# IN_conditioning.net
KiCad netlist of a schematic drawn in Altium Designer
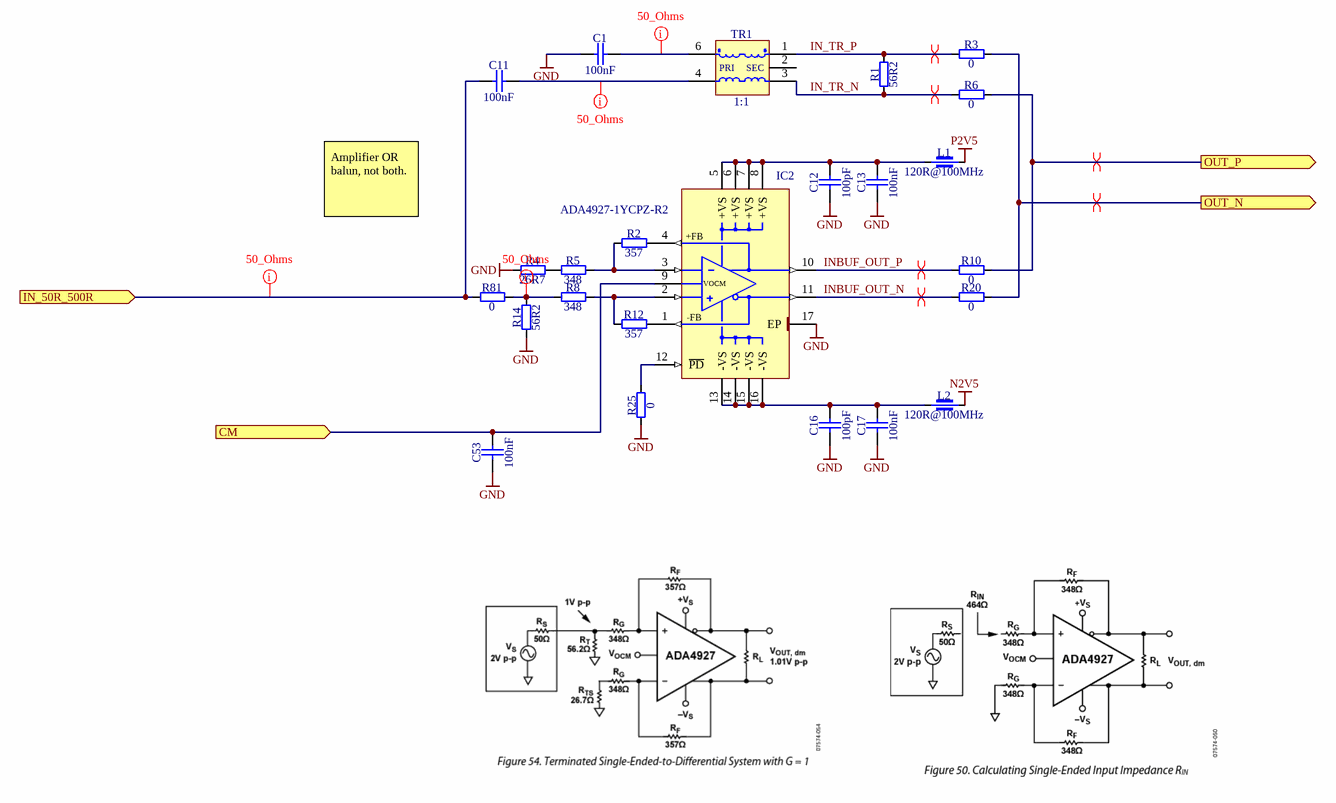
[diagram p0: IN_conditioning.SchDoc]

(export (version "E")
  (design (tool "Eeschema 10.0.6"))
  (components
    (comp (ref "C1")
      (value "100nF")
      (footprint "CAPC1005X55N")
      (description "Non-polarised capacitor")
      (fields
        (field (name "PART NUMBER") "CC0402_100NF_16V_10%_X5R")
        (field (name "VOLTAGE") "16V")
        (field (name "AUTHOR") "CERN DEM JLC")
      )
      (libsource (lib "Capacitors") (part "Capacitor - non polarized"))
    )
    (comp (ref "C11")
      (value "100nF")
      (footprint "CAPC1005X55N")
      (description "Non-polarised capacitor")
      (fields
        (field (name "PART NUMBER") "CC0402_100NF_16V_10%_X5R")
        (field (name "VOLTAGE") "16V")
        (field (name "AUTHOR") "CERN DEM JLC")
      )
      (libsource (lib "Capacitors") (part "Capacitor - non polarized"))
    )
    (comp (ref "C12")
      (value "100pF")
      (footprint "CAPC1005X55N")
      (description "Non-polarised capacitor")
      (fields
        (field (name "PART NUMBER") "CC0402_100PF_50V_2%_C0G")
        (field (name "VOLTAGE") "50V")
        (field (name "AUTHOR") "CERN DEM BC")
      )
      (libsource (lib "Capacitors") (part "Capacitor - non polarized"))
    )
    (comp (ref "C13")
      (value "100nF")
      (footprint "CAPC1005X55N")
      (description "Non-polarised capacitor")
      (fields
        (field (name "PART NUMBER") "CC0402_100NF_16V_10%_X5R")
        (field (name "VOLTAGE") "16V")
        (field (name "AUTHOR") "CERN DEM JLC")
      )
      (libsource (lib "Capacitors") (part "Capacitor - non polarized"))
    )
    (comp (ref "C16")
      (value "100pF")
      (footprint "CAPC1005X55N")
      (description "Non-polarised capacitor")
      (fields
        (field (name "PART NUMBER") "CC0402_100PF_50V_2%_C0G")
        (field (name "VOLTAGE") "50V")
        (field (name "AUTHOR") "CERN DEM BC")
      )
      (libsource (lib "Capacitors") (part "Capacitor - non polarized"))
    )
    (comp (ref "C17")
      (value "100nF")
      (footprint "CAPC1005X55N")
      (description "Non-polarised capacitor")
      (fields
        (field (name "PART NUMBER") "CC0402_100NF_16V_10%_X5R")
        (field (name "VOLTAGE") "16V")
        (field (name "AUTHOR") "CERN DEM JLC")
      )
      (libsource (lib "Capacitors") (part "Capacitor - non polarized"))
    )
    (comp (ref "C53")
      (value "100nF")
      (footprint "CAPC1005X55N")
      (description "Non-polarised capacitor")
      (fields
        (field (name "PART NUMBER") "CC0402_100NF_16V_10%_X5R")
        (field (name "VOLTAGE") "16V")
        (field (name "AUTHOR") "CERN DEM JLC")
      )
      (libsource (lib "Capacitors") (part "Capacitor - non polarized"))
    )
    (comp (ref "IC2")
      (value "ADA4927-1YCPZ-R2")
      (footprint "QFN50P300X300X100-17N-S145")
      (description "Ultralow Distortion Current Feedback Differential ADC Driver")
      (fields
        (field (name "MANUFACTURER") "ANALOG DEVICES")
        (field (name "MANUFACTURER PART NUMBER") "ADA4927-1YCP")
        (field (name "AUTHOR") "CERN DEM JLC")
      )
      (libsource (lib "ICs And Semiconductors") (part "ADA4927-1"))
    )
    (comp (ref "L1")
      (value "120R@100MHz")
      (footprint "INDC1005X55N")
      (fields
        (field (name "PART NUMBER") "IND0402_MURATA_BLM15PX121SN1D")
        (field (name "POWER") "2A")
        (field (name "TOLERANCE") "±25%")
        (field (name "AUTHOR") "CERN DEM JMW")
      )
      (libsource (lib "Inductors & Transformers") (part "Ferrite Bead"))
    )
    (comp (ref "L2")
      (value "120R@100MHz")
      (footprint "INDC1005X55N")
      (fields
        (field (name "PART NUMBER") "IND0402_MURATA_BLM15PX121SN1D")
        (field (name "POWER") "2A")
        (field (name "TOLERANCE") "±25%")
        (field (name "AUTHOR") "CERN DEM JMW")
      )
      (libsource (lib "Inductors & Transformers") (part "Ferrite Bead"))
    )
    (comp (ref "R1")
      (value "56R2")
      (footprint "RESC1005X40N")
      (description "Resistor - 1%")
      (fields
        (field (name "PART NUMBER") "R0402_56R2_1%_0.063W_50PPM")
        (field (name "MANUFACTURER") "GENERIC")
        (field (name "AUTHOR") "SHA")
      )
      (libsource (lib "Modulator_pLib") (part "R0402_56R2_1%_0.063W_50PPM"))
    )
    (comp (ref "R2")
      (value "357")
      (footprint "RESC1005X40N")
      (description "Resistor - 0.1%")
      (fields
        (field (name "PART NUMBER") "R0402_357R_0.1%_0.063W_25PPM")
        (field (name "MANUFACTURER") "GENERIC")
        (field (name "AUTHOR") "SHA")
      )
      (libsource (lib "Modulator_pLib") (part "R0402_357R_0.1%_0.063W_50PPM"))
    )
    (comp (ref "R3")
      (value "0")
      (footprint "RESC1005X40N")
      (description "Resistor")
      (fields
        (field (name "PART NUMBER") "R0402_0R_JUMPER")
        (field (name "MANUFACTURER") "GENERIC")
        (field (name "AUTHOR") "CERN DEM JLC")
      )
      (libsource (lib "Resistors") (part "Resistor"))
    )
    (comp (ref "R4")
      (value "26R7")
      (footprint "RESC1005X40N")
      (description "Resistor - 1%")
      (fields
        (field (name "PART NUMBER") "R0402_26R7_1%_0.063W_100PPM")
        (field (name "MANUFACTURER") "GENERIC")
        (field (name "AUTHOR") "SHA")
      )
      (libsource (lib "Modulator_pLib") (part "R0402_26R7_1%_0.063W_100PPM"))
    )
    (comp (ref "R5")
      (value "348")
      (footprint "RESC1005X40N")
      (description "Resistor - 0.1%")
      (fields
        (field (name "PART NUMBER") "R0402_348R_0.1%_0.063W_25PPM")
        (field (name "MANUFACTURER") "GENERIC")
        (field (name "AUTHOR") "SHA")
      )
      (libsource (lib "Modulator_pLib") (part "R0402_348R_0.1%_0.063W_25PPM"))
    )
    (comp (ref "R6")
      (value "0")
      (footprint "RESC1005X40N")
      (description "Resistor")
      (fields
        (field (name "PART NUMBER") "R0402_0R_JUMPER")
        (field (name "MANUFACTURER") "GENERIC")
        (field (name "AUTHOR") "CERN DEM JLC")
      )
      (libsource (lib "Resistors") (part "Resistor"))
    )
    (comp (ref "R8")
      (value "348")
      (footprint "RESC1005X40N")
      (description "Resistor - 0.1%")
      (fields
        (field (name "PART NUMBER") "R0402_348R_0.1%_0.063W_25PPM")
        (field (name "MANUFACTURER") "GENERIC")
        (field (name "AUTHOR") "SHA")
      )
      (libsource (lib "Modulator_pLib") (part "R0402_348R_0.1%_0.063W_25PPM"))
    )
    (comp (ref "R10")
      (value "0")
      (footprint "RESC1005X40N")
      (description "Resistor")
      (fields
        (field (name "PART NUMBER") "R0402_0R_JUMPER")
        (field (name "MANUFACTURER") "GENERIC")
        (field (name "AUTHOR") "CERN DEM JLC")
      )
      (libsource (lib "Resistors") (part "Resistor"))
    )
    (comp (ref "R12")
      (value "357")
      (footprint "RESC1005X40N")
      (description "Resistor - 0.1%")
      (fields
        (field (name "PART NUMBER") "R0402_357R_0.1%_0.063W_25PPM")
        (field (name "MANUFACTURER") "GENERIC")
        (field (name "AUTHOR") "SHA")
      )
      (libsource (lib "Modulator_pLib") (part "R0402_357R_0.1%_0.063W_50PPM"))
    )
    (comp (ref "R14")
      (value "56R2")
      (footprint "RESC1005X40N")
      (description "Resistor - 1%")
      (fields
        (field (name "PART NUMBER") "R0402_56R2_1%_0.063W_50PPM")
        (field (name "MANUFACTURER") "GENERIC")
        (field (name "AUTHOR") "SHA")
      )
      (libsource (lib "Modulator_pLib") (part "R0402_56R2_1%_0.063W_50PPM"))
    )
    (comp (ref "R20")
      (value "0")
      (footprint "RESC1005X40N")
      (description "Resistor")
      (fields
        (field (name "PART NUMBER") "R0402_0R_JUMPER")
        (field (name "MANUFACTURER") "GENERIC")
        (field (name "AUTHOR") "CERN DEM JLC")
      )
      (libsource (lib "Resistors") (part "Resistor"))
    )
    (comp (ref "R25")
      (value "0")
      (footprint "RESC1005X40N")
      (description "Resistor")
      (fields
        (field (name "PART NUMBER") "R0402_0R_JUMPER")
        (field (name "MANUFACTURER") "GENERIC")
        (field (name "AUTHOR") "CERN DEM JLC")
      )
      (libsource (lib "Resistors") (part "Resistor"))
    )
    (comp (ref "R81")
      (value "0")
      (footprint "RESC1005X40N")
      (description "Resistor")
      (fields
        (field (name "PART NUMBER") "R0402_0R_JUMPER")
        (field (name "MANUFACTURER") "GENERIC")
        (field (name "AUTHOR") "CERN DEM JLC")
      )
      (libsource (lib "Resistors") (part "Resistor"))
    )
    (comp (ref "TR1")
      (value "1:1")
      (footprint "XFMR_MINI-CIRCUITS_AT224")
      (description "50 Ohms 4.5 To 3000MHz RF Transformers")
      (fields
        (field (name "PART NUMBER") "XFMR_MINI-CIRCUITS_TC1-1-13M+")
        (field (name "MANUFACTURER") "MINI-CIRCUITS")
        (field (name "AUTHOR") "CERN DEM JLC")
      )
      (libsource (lib "Inductors & Transformers") (part "XFMR_MINI-CIRCUITS_TC1-1-13M+"))
    )
  )
  (nets
    (net (code "1") (name "/CM") (class "Default")
      (node (ref "C53") (pin "2") (pinfunction "2_2") (pintype "passive"))
      (node (ref "IC2") (pin "9") (pinfunction "VOCM_9") (pintype "passive"))
    )
    (net (code "2") (name "/INBUF_OUT_N") (class "Default")
      (node (ref "IC2") (pin "11") (pinfunction "-OUT_11") (pintype "output"))
      (node (ref "R20") (pin "1") (pinfunction "1_1") (pintype "passive"))
    )
    (net (code "3") (name "/INBUF_OUT_P") (class "Default")
      (node (ref "IC2") (pin "10") (pinfunction "+OUT_10") (pintype "output"))
      (node (ref "R10") (pin "1") (pinfunction "1_1") (pintype "passive"))
    )
    (net (code "4") (name "/IN_50R_500R") (class "Default")
      (node (ref "C11") (pin "1") (pinfunction "1_1") (pintype "passive"))
      (node (ref "R81") (pin "1") (pinfunction "1_1") (pintype "passive"))
    )
    (net (code "5") (name "/IN_TR_N") (class "Default")
      (node (ref "R1") (pin "1") (pinfunction "1_1") (pintype "passive"))
      (node (ref "R6") (pin "1") (pinfunction "1_1") (pintype "passive"))
      (node (ref "TR1") (pin "3") (pinfunction "S_3") (pintype "passive"))
    )
    (net (code "6") (name "/IN_TR_P") (class "Default")
      (node (ref "R1") (pin "2") (pinfunction "2_2") (pintype "passive"))
      (node (ref "R3") (pin "1") (pinfunction "1_1") (pintype "passive"))
      (node (ref "TR1") (pin "1") (pinfunction "SDOT_1") (pintype "passive"))
    )
    (net (code "7") (name "/OUT_N") (class "Default")
      (node (ref "R20") (pin "2") (pinfunction "2_2") (pintype "passive"))
      (node (ref "R3") (pin "2") (pinfunction "2_2") (pintype "passive"))
    )
    (net (code "8") (name "/OUT_P") (class "Default")
      (node (ref "R10") (pin "2") (pinfunction "2_2") (pintype "passive"))
      (node (ref "R6") (pin "2") (pinfunction "2_2") (pintype "passive"))
    )
    (net (code "9") (name "GND") (class "Default")
      (node (ref "C1") (pin "1") (pinfunction "1_1") (pintype "passive"))
      (node (ref "C12") (pin "1") (pinfunction "1_1") (pintype "passive"))
      (node (ref "C13") (pin "1") (pinfunction "1_1") (pintype "passive"))
      (node (ref "C16") (pin "1") (pinfunction "1_1") (pintype "passive"))
      (node (ref "C17") (pin "1") (pinfunction "1_1") (pintype "passive"))
      (node (ref "C53") (pin "1") (pinfunction "1_1") (pintype "passive"))
      (node (ref "IC2") (pin "17") (pinfunction "EP_17") (pintype "power_in"))
      (node (ref "R14") (pin "1") (pinfunction "1_1") (pintype "passive"))
      (node (ref "R25") (pin "1") (pinfunction "1_1") (pintype "passive"))
      (node (ref "R4") (pin "1") (pinfunction "1_1") (pintype "passive"))
    )
    (net (code "10") (name "N2V5") (class "Default")
      (node (ref "L2") (pin "2") (pinfunction "2_2") (pintype "passive"))
    )
    (net (code "11") (name "Net-(C12-Pad2)") (class "Default")
      (node (ref "C12") (pin "2") (pinfunction "2_2") (pintype "passive"))
      (node (ref "C13") (pin "2") (pinfunction "2_2") (pintype "passive"))
      (node (ref "IC2") (pin "5") (pinfunction "+VS_5") (pintype "power_in"))
      (node (ref "IC2") (pin "6") (pinfunction "+VS_6") (pintype "power_in"))
      (node (ref "IC2") (pin "7") (pinfunction "+VS_7") (pintype "power_in"))
      (node (ref "IC2") (pin "8") (pinfunction "+VS_8") (pintype "power_in"))
      (node (ref "L1") (pin "1") (pinfunction "1_1") (pintype "passive"))
    )
    (net (code "12") (name "Net-(C16-Pad2)") (class "Default")
      (node (ref "C16") (pin "2") (pinfunction "2_2") (pintype "passive"))
      (node (ref "C17") (pin "2") (pinfunction "2_2") (pintype "passive"))
      (node (ref "IC2") (pin "13") (pinfunction "-VS_13") (pintype "power_in"))
      (node (ref "IC2") (pin "14") (pinfunction "-VS_14") (pintype "power_in"))
      (node (ref "IC2") (pin "15") (pinfunction "-VS_15") (pintype "power_in"))
      (node (ref "IC2") (pin "16") (pinfunction "-VS_16") (pintype "power_in"))
      (node (ref "L2") (pin "1") (pinfunction "1_1") (pintype "passive"))
    )
    (net (code "13") (name "Net-(IC2-+FB)") (class "Default")
      (node (ref "IC2") (pin "4") (pinfunction "+FB_4") (pintype "output"))
      (node (ref "R2") (pin "2") (pinfunction "2_2") (pintype "passive"))
    )
    (net (code "14") (name "Net-(IC2-+IN)") (class "Default")
      (node (ref "IC2") (pin "2") (pinfunction "+IN_2") (pintype "input"))
      (node (ref "R12") (pin "1") (pinfunction "1_1") (pintype "passive"))
      (node (ref "R8") (pin "2") (pinfunction "2_2") (pintype "passive"))
    )
    (net (code "15") (name "Net-(IC2--FB)") (class "Default")
      (node (ref "IC2") (pin "1") (pinfunction "-FB_1") (pintype "output"))
      (node (ref "R12") (pin "2") (pinfunction "2_2") (pintype "passive"))
    )
    (net (code "16") (name "Net-(IC2--IN)") (class "Default")
      (node (ref "IC2") (pin "3") (pinfunction "-IN_3") (pintype "input"))
      (node (ref "R2") (pin "1") (pinfunction "1_1") (pintype "passive"))
      (node (ref "R5") (pin "2") (pinfunction "2_2") (pintype "passive"))
    )
    (net (code "17") (name "Net-(IC2-~{PD})") (class "Default")
      (node (ref "IC2") (pin "12") (pinfunction "~{PD}_12") (pintype "input"))
      (node (ref "R25") (pin "2") (pinfunction "2_2") (pintype "passive"))
    )
    (net (code "18") (name "Net-(R4-Pad2)") (class "Default")
      (node (ref "R4") (pin "2") (pinfunction "2_2") (pintype "passive"))
      (node (ref "R5") (pin "1") (pinfunction "1_1") (pintype "passive"))
    )
    (net (code "19") (name "Net-(R14-Pad2)") (class "Default")
      (node (ref "R14") (pin "2") (pinfunction "2_2") (pintype "passive"))
      (node (ref "R8") (pin "1") (pinfunction "1_1") (pintype "passive"))
      (node (ref "R81") (pin "2") (pinfunction "2_2") (pintype "passive"))
    )
    (net (code "20") (name "Net-(TR1-P)") (class "Default")
      (node (ref "C11") (pin "2") (pinfunction "2_2") (pintype "passive"))
      (node (ref "TR1") (pin "4") (pinfunction "P_4") (pintype "passive"))
    )
    (net (code "21") (name "Net-(TR1-PDOT)") (class "Default")
      (node (ref "C1") (pin "2") (pinfunction "2_2") (pintype "passive"))
      (node (ref "TR1") (pin "6") (pinfunction "PDOT_6") (pintype "passive"))
    )
    (net (code "22") (name "P2V5") (class "Default")
      (node (ref "L1") (pin "2") (pinfunction "2_2") (pintype "passive"))
    )
    (net (code "23") (name "unconnected-(TR1-NC-Pad2)") (class "Default")
      (node (ref "TR1") (pin "2") (pinfunction "NC_2") (pintype "passive"))
    )
  )
)
